# DD2090_4CAM_FFC_Connector_B.net
KiCad netlist of a schematic drawn in Altium Designer
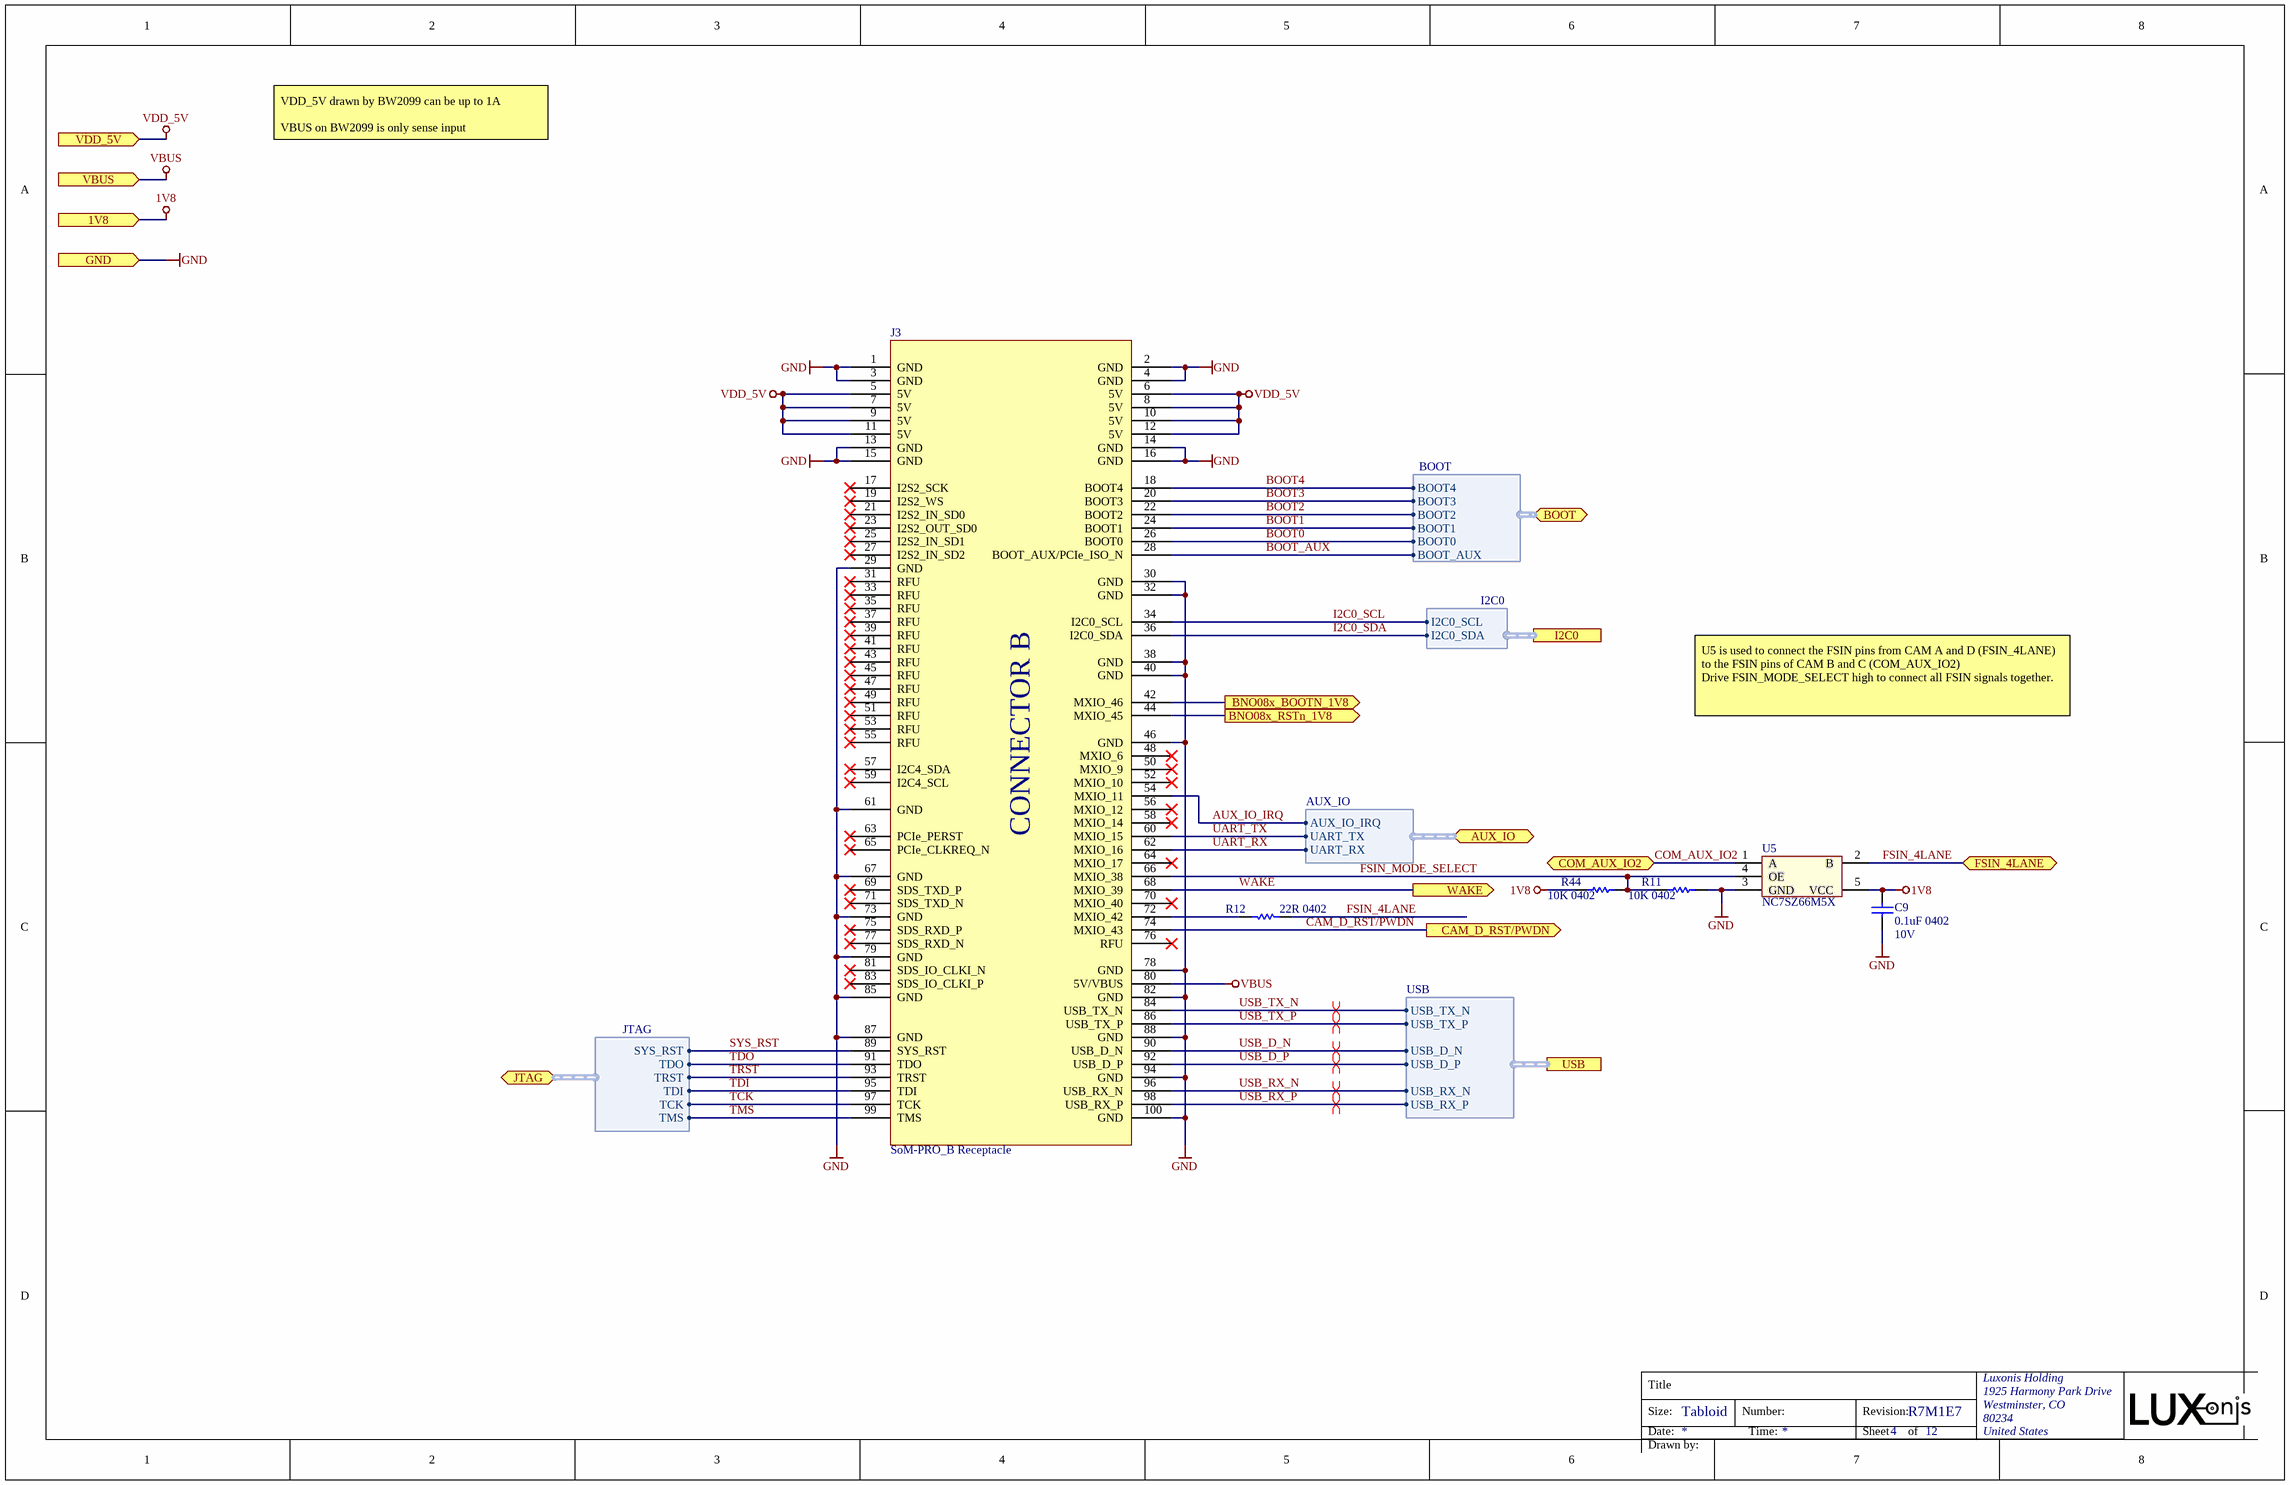
[diagram p0: DD2090_4CAM_FFC_Connector_B.SchDoc]

(export (version "E")
  (design (tool "Eeschema 10.0.6"))
  (components
    (comp (ref "C9")
      (value "0.1uF 0402")
      (footprint "CAPC0402(1005)70_L")
      (description "CAP CER 0.1UF 10V X7R 0402 5%")
      (fields (field (name "TOLERANCE") "5%") (field (name "VOLTAGE RATING") "10V"))
      (libsource (lib "LuxonisMaster") (part "GRM155R71A104JA01D"))
    )
    (comp (ref "J3")
      (value "SoM-PRO_B Receptacle")
      (footprint "LuxonisMaster:CON_B_BW2099_SoM_DF40HC-3.0-100DS-0.4V_minpad")
      (description "CONN RCPT 100POS 0.4MM SMD GOLD")
      (libsource (lib "LuxonisMaster") (part "DF40HC(3.0)-100DS-0.4V_SoM-PRO_B"))
    )
    (comp (ref "R11")
      (value "10K 0402")
      (footprint "RESC0402(1005)_L")
      (fields (field (name "TOLERANCE") "1%"))
      (libsource (lib "LuxonisMaster") (part "RC0402FR-1310KL"))
    )
    (comp (ref "R12")
      (value "22R 0402")
      (footprint "RESC0402(1005)_N")
      (description "RES SMD 22 OHM 1% 1/16W 0402")
      (fields (field (name "TOLERANCE") "1%"))
      (libsource (lib "BW2098POE") (part "RC0402FR-0722RL"))
    )
    (comp (ref "R44")
      (value "10K 0402")
      (footprint "RESC0402(1005)_L")
      (fields (field (name "TOLERANCE") "1%"))
      (libsource (lib "LuxonisMaster") (part "RC0402FR-1310KL"))
    )
    (comp (ref "U5")
      (value "NC7SZ66M5X")
      (footprint "SOT235")
      (fields (field (name "VOLTAGE") "5V"))
      (libsource (lib "DD2099_4CAM_FFC") (part "NC7SZ66M5X"))
    )
  )
  (nets
    (net (code "6") (name "/AUX_IO_IRQ") (class "Default")
      (node (ref "J3") (pin "54") (pinfunction "MXIO_11_54") (pintype "passive"))
    )
    (net (code "7") (name "/BNO08x_BOOTN_1V8") (class "Default")
      (node (ref "J3") (pin "42") (pinfunction "MXIO_46_42") (pintype "passive"))
    )
    (net (code "8") (name "/BNO08x_RSTn_1V8") (class "Default")
      (node (ref "J3") (pin "44") (pinfunction "MXIO_45_44") (pintype "passive"))
    )
    (net (code "9") (name "/BOOT0") (class "Default")
      (node (ref "J3") (pin "26") (pinfunction "BOOT0_26") (pintype "passive"))
    )
    (net (code "10") (name "/BOOT1") (class "Default")
      (node (ref "J3") (pin "24") (pinfunction "BOOT1_24") (pintype "passive"))
    )
    (net (code "11") (name "/BOOT2") (class "Default")
      (node (ref "J3") (pin "22") (pinfunction "BOOT2_22") (pintype "passive"))
    )
    (net (code "12") (name "/BOOT3") (class "Default")
      (node (ref "J3") (pin "20") (pinfunction "BOOT3_20") (pintype "passive"))
    )
    (net (code "13") (name "/BOOT4") (class "Default")
      (node (ref "J3") (pin "18") (pinfunction "BOOT4_18") (pintype "passive"))
    )
    (net (code "14") (name "/BOOT_AUX") (class "Default")
      (node (ref "J3") (pin "28") (pinfunction "BOOT_AUX/PCIe_ISO_N_28") (pintype "passive"))
    )
    (net (code "15") (name "/CAM_D_RST{slash}PWDN") (class "Default")
      (node (ref "J3") (pin "74") (pinfunction "MXIO_43_74") (pintype "passive"))
    )
    (net (code "16") (name "/COM_AUX_IO2") (class "Default")
      (node (ref "U5") (pin "1") (pinfunction "A_1") (pintype "passive"))
    )
    (net (code "17") (name "/FSIN_4LANE") (class "Default")
      (node (ref "R12") (pin "1") (pinfunction "1_1") (pintype "passive"))
      (node (ref "U5") (pin "2") (pinfunction "B_2") (pintype "passive"))
    )
    (net (code "18") (name "/FSIN_MODE_SELECT") (class "Default")
      (node (ref "J3") (pin "66") (pinfunction "MXIO_38_66") (pintype "passive"))
      (node (ref "R11") (pin "2") (pinfunction "2_2") (pintype "passive"))
      (node (ref "R44") (pin "1") (pinfunction "1_1") (pintype "passive"))
      (node (ref "U5") (pin "4") (pinfunction "OE_4") (pintype "passive"))
    )
    (net (code "19") (name "/I2C0_SCL") (class "Default")
      (node (ref "J3") (pin "34") (pinfunction "I2C0_SCL_34") (pintype "passive"))
    )
    (net (code "20") (name "/I2C0_SDA") (class "Default")
      (node (ref "J3") (pin "36") (pinfunction "I2C0_SDA_36") (pintype "passive"))
    )
    (net (code "21") (name "/SYS_RST") (class "Default")
      (node (ref "J3") (pin "89") (pinfunction "SYS_RST_89") (pintype "passive"))
    )
    (net (code "22") (name "/TCK") (class "Default")
      (node (ref "J3") (pin "97") (pinfunction "TCK_97") (pintype "passive"))
    )
    (net (code "23") (name "/TDI") (class "Default")
      (node (ref "J3") (pin "95") (pinfunction "TDI_95") (pintype "passive"))
    )
    (net (code "24") (name "/TDO") (class "Default")
      (node (ref "J3") (pin "91") (pinfunction "TDO_91") (pintype "passive"))
    )
    (net (code "25") (name "/TMS") (class "Default")
      (node (ref "J3") (pin "99") (pinfunction "TMS_99") (pintype "passive"))
    )
    (net (code "26") (name "/TRST") (class "Default")
      (node (ref "J3") (pin "93") (pinfunction "TRST_93") (pintype "passive"))
    )
    (net (code "27") (name "/UART_RX") (class "Default")
      (node (ref "J3") (pin "62") (pinfunction "MXIO_16_62") (pintype "passive"))
    )
    (net (code "28") (name "/UART_TX") (class "Default")
      (node (ref "J3") (pin "60") (pinfunction "MXIO_15_60") (pintype "passive"))
    )
    (net (code "29") (name "/USB_D_N") (class "Default")
      (node (ref "J3") (pin "90") (pinfunction "USB_D_N_90") (pintype "passive"))
    )
    (net (code "30") (name "/USB_D_P") (class "Default")
      (node (ref "J3") (pin "92") (pinfunction "USB_D_P_92") (pintype "passive"))
    )
    (net (code "31") (name "/USB_RX_N") (class "Default")
      (node (ref "J3") (pin "96") (pinfunction "USB_RX_N_96") (pintype "passive"))
    )
    (net (code "32") (name "/USB_RX_P") (class "Default")
      (node (ref "J3") (pin "98") (pinfunction "USB_RX_P_98") (pintype "passive"))
    )
    (net (code "33") (name "/USB_TX_N") (class "Default")
      (node (ref "J3") (pin "84") (pinfunction "USB_TX_N_84") (pintype "passive"))
    )
    (net (code "34") (name "/USB_TX_P") (class "Default")
      (node (ref "J3") (pin "86") (pinfunction "USB_TX_P_86") (pintype "passive"))
    )
    (net (code "35") (name "/WAKE") (class "Default")
      (node (ref "J3") (pin "68") (pinfunction "MXIO_39_68") (pintype "passive"))
    )
    (net (code "41") (name "1V8") (class "Default")
      (node (ref "C9") (pin "2") (pinfunction "2_2") (pintype "passive"))
      (node (ref "R44") (pin "2") (pinfunction "2_2") (pintype "passive"))
      (node (ref "U5") (pin "5") (pinfunction "VCC_5") (pintype "passive"))
    )
    (net (code "42") (name "GND") (class "Default")
      (node (ref "C9") (pin "1") (pinfunction "1_1") (pintype "passive"))
      (node (ref "J3") (pin "1") (pinfunction "GND_1") (pintype "passive"))
      (node (ref "J3") (pin "100") (pinfunction "GND_100") (pintype "passive"))
      (node (ref "J3") (pin "13") (pinfunction "GND_13") (pintype "passive"))
      (node (ref "J3") (pin "14") (pinfunction "GND_14") (pintype "passive"))
      (node (ref "J3") (pin "15") (pinfunction "GND_15") (pintype "passive"))
      (node (ref "J3") (pin "16") (pinfunction "GND_16") (pintype "passive"))
      (node (ref "J3") (pin "2") (pinfunction "GND_2") (pintype "passive"))
      (node (ref "J3") (pin "29") (pinfunction "GND_29") (pintype "passive"))
      (node (ref "J3") (pin "3") (pinfunction "GND_3") (pintype "passive"))
      (node (ref "J3") (pin "30") (pinfunction "GND_30") (pintype "passive"))
      (node (ref "J3") (pin "32") (pinfunction "GND_32") (pintype "passive"))
      (node (ref "J3") (pin "38") (pinfunction "GND_38") (pintype "passive"))
      (node (ref "J3") (pin "4") (pinfunction "GND_4") (pintype "passive"))
      (node (ref "J3") (pin "40") (pinfunction "GND_40") (pintype "passive"))
      (node (ref "J3") (pin "46") (pinfunction "GND_46") (pintype "passive"))
      (node (ref "J3") (pin "61") (pinfunction "GND_61") (pintype "passive"))
      (node (ref "J3") (pin "67") (pinfunction "GND_67") (pintype "passive"))
      (node (ref "J3") (pin "73") (pinfunction "GND_73") (pintype "passive"))
      (node (ref "J3") (pin "78") (pinfunction "GND_78") (pintype "passive"))
      (node (ref "J3") (pin "79") (pinfunction "GND_79") (pintype "passive"))
      (node (ref "J3") (pin "82") (pinfunction "GND_82") (pintype "passive"))
      (node (ref "J3") (pin "85") (pinfunction "GND_85") (pintype "passive"))
      (node (ref "J3") (pin "87") (pinfunction "GND_87") (pintype "passive"))
      (node (ref "J3") (pin "88") (pinfunction "GND_88") (pintype "passive"))
      (node (ref "J3") (pin "94") (pinfunction "GND_94") (pintype "passive"))
      (node (ref "R11") (pin "1") (pinfunction "1_1") (pintype "passive"))
      (node (ref "U5") (pin "3") (pinfunction "GND_3") (pintype "passive"))
    )
    (net (code "43") (name "Net-(J3-MXIO_42)") (class "Default")
      (node (ref "J3") (pin "72") (pinfunction "MXIO_42_72") (pintype "passive"))
      (node (ref "R12") (pin "2") (pinfunction "2_2") (pintype "passive"))
    )
    (net (code "44") (name "VBUS") (class "Default")
      (node (ref "J3") (pin "80") (pinfunction "5V/VBUS_80") (pintype "passive"))
    )
    (net (code "45") (name "VDD_5V") (class "Default")
      (node (ref "J3") (pin "10") (pinfunction "5V_10") (pintype "passive"))
      (node (ref "J3") (pin "11") (pinfunction "5V_11") (pintype "passive"))
      (node (ref "J3") (pin "12") (pinfunction "5V_12") (pintype "passive"))
      (node (ref "J3") (pin "5") (pinfunction "5V_5") (pintype "passive"))
      (node (ref "J3") (pin "6") (pinfunction "5V_6") (pintype "passive"))
      (node (ref "J3") (pin "7") (pinfunction "5V_7") (pintype "passive"))
      (node (ref "J3") (pin "8") (pinfunction "5V_8") (pintype "passive"))
      (node (ref "J3") (pin "9") (pinfunction "5V_9") (pintype "passive"))
    )
    (net (code "46") (name "unconnected-(J3-I2C4_SCL-Pad59)") (class "Default")
      (node (ref "J3") (pin "59") (pinfunction "I2C4_SCL_59") (pintype "passive+no_connect"))
    )
    (net (code "47") (name "unconnected-(J3-I2C4_SDA-Pad57)") (class "Default")
      (node (ref "J3") (pin "57") (pinfunction "I2C4_SDA_57") (pintype "passive+no_connect"))
    )
    (net (code "48") (name "unconnected-(J3-I2S2_IN_SD0-Pad21)") (class "Default")
      (node (ref "J3") (pin "21") (pinfunction "I2S2_IN_SD0_21") (pintype "passive+no_connect"))
    )
    (net (code "49") (name "unconnected-(J3-I2S2_IN_SD1-Pad25)") (class "Default")
      (node (ref "J3") (pin "25") (pinfunction "I2S2_IN_SD1_25") (pintype "passive+no_connect"))
    )
    (net (code "50") (name "unconnected-(J3-I2S2_IN_SD2-Pad27)") (class "Default")
      (node (ref "J3") (pin "27") (pinfunction "I2S2_IN_SD2_27") (pintype "passive+no_connect"))
    )
    (net (code "51") (name "unconnected-(J3-I2S2_OUT_SD0-Pad23)") (class "Default")
      (node (ref "J3") (pin "23") (pinfunction "I2S2_OUT_SD0_23") (pintype "passive+no_connect"))
    )
    (net (code "52") (name "unconnected-(J3-I2S2_SCK-Pad17)") (class "Default")
      (node (ref "J3") (pin "17") (pinfunction "I2S2_SCK_17") (pintype "passive+no_connect"))
    )
    (net (code "53") (name "unconnected-(J3-I2S2_WS-Pad19)") (class "Default")
      (node (ref "J3") (pin "19") (pinfunction "I2S2_WS_19") (pintype "passive+no_connect"))
    )
    (net (code "54") (name "unconnected-(J3-MXIO_6-Pad48)") (class "Default")
      (node (ref "J3") (pin "48") (pinfunction "MXIO_6_48") (pintype "passive+no_connect"))
    )
    (net (code "55") (name "unconnected-(J3-MXIO_9-Pad50)") (class "Default")
      (node (ref "J3") (pin "50") (pinfunction "MXIO_9_50") (pintype "passive+no_connect"))
    )
    (net (code "56") (name "unconnected-(J3-MXIO_10-Pad52)") (class "Default")
      (node (ref "J3") (pin "52") (pinfunction "MXIO_10_52") (pintype "passive+no_connect"))
    )
    (net (code "57") (name "unconnected-(J3-MXIO_12-Pad56)") (class "Default")
      (node (ref "J3") (pin "56") (pinfunction "MXIO_12_56") (pintype "passive+no_connect"))
    )
    (net (code "58") (name "unconnected-(J3-MXIO_14-Pad58)") (class "Default")
      (node (ref "J3") (pin "58") (pinfunction "MXIO_14_58") (pintype "passive+no_connect"))
    )
    (net (code "59") (name "unconnected-(J3-MXIO_17-Pad64)") (class "Default")
      (node (ref "J3") (pin "64") (pinfunction "MXIO_17_64") (pintype "passive+no_connect"))
    )
    (net (code "60") (name "unconnected-(J3-MXIO_40-Pad70)") (class "Default")
      (node (ref "J3") (pin "70") (pinfunction "MXIO_40_70") (pintype "passive+no_connect"))
    )
    (net (code "61") (name "unconnected-(J3-PCIe_CLKREQ_N-Pad65)") (class "Default")
      (node (ref "J3") (pin "65") (pinfunction "PCIe_CLKREQ_N_65") (pintype "passive+no_connect"))
    )
    (net (code "62") (name "unconnected-(J3-PCIe_PERST-Pad63)") (class "Default")
      (node (ref "J3") (pin "63") (pinfunction "PCIe_PERST_63") (pintype "passive+no_connect"))
    )
    (net (code "63") (name "unconnected-(J3-RFU-Pad31)") (class "Default")
      (node (ref "J3") (pin "31") (pinfunction "RFU_31") (pintype "passive+no_connect"))
    )
    (net (code "64") (name "unconnected-(J3-RFU-Pad33)") (class "Default")
      (node (ref "J3") (pin "33") (pinfunction "RFU_33") (pintype "passive+no_connect"))
    )
    (net (code "65") (name "unconnected-(J3-RFU-Pad35)") (class "Default")
      (node (ref "J3") (pin "35") (pinfunction "RFU_35") (pintype "passive+no_connect"))
    )
    (net (code "66") (name "unconnected-(J3-RFU-Pad37)") (class "Default")
      (node (ref "J3") (pin "37") (pinfunction "RFU_37") (pintype "passive+no_connect"))
    )
    (net (code "67") (name "unconnected-(J3-RFU-Pad39)") (class "Default")
      (node (ref "J3") (pin "39") (pinfunction "RFU_39") (pintype "passive+no_connect"))
    )
    (net (code "68") (name "unconnected-(J3-RFU-Pad41)") (class "Default")
      (node (ref "J3") (pin "41") (pinfunction "RFU_41") (pintype "passive+no_connect"))
    )
    (net (code "69") (name "unconnected-(J3-RFU-Pad43)") (class "Default")
      (node (ref "J3") (pin "43") (pinfunction "RFU_43") (pintype "passive+no_connect"))
    )
    (net (code "70") (name "unconnected-(J3-RFU-Pad45)") (class "Default")
      (node (ref "J3") (pin "45") (pinfunction "RFU_45") (pintype "passive+no_connect"))
    )
    (net (code "71") (name "unconnected-(J3-RFU-Pad47)") (class "Default")
      (node (ref "J3") (pin "47") (pinfunction "RFU_47") (pintype "passive+no_connect"))
    )
    (net (code "72") (name "unconnected-(J3-RFU-Pad49)") (class "Default")
      (node (ref "J3") (pin "49") (pinfunction "RFU_49") (pintype "passive+no_connect"))
    )
    (net (code "73") (name "unconnected-(J3-RFU-Pad51)") (class "Default")
      (node (ref "J3") (pin "51") (pinfunction "RFU_51") (pintype "passive+no_connect"))
    )
    (net (code "74") (name "unconnected-(J3-RFU-Pad53)") (class "Default")
      (node (ref "J3") (pin "53") (pinfunction "RFU_53") (pintype "passive+no_connect"))
    )
    (net (code "75") (name "unconnected-(J3-RFU-Pad55)") (class "Default")
      (node (ref "J3") (pin "55") (pinfunction "RFU_55") (pintype "passive+no_connect"))
    )
    (net (code "76") (name "unconnected-(J3-RFU-Pad76)") (class "Default")
      (node (ref "J3") (pin "76") (pinfunction "RFU_76") (pintype "passive+no_connect"))
    )
    (net (code "77") (name "unconnected-(J3-SDS_IO_CLKI_N-Pad81)") (class "Default")
      (node (ref "J3") (pin "81") (pinfunction "SDS_IO_CLKI_N_81") (pintype "passive+no_connect"))
    )
    (net (code "78") (name "unconnected-(J3-SDS_IO_CLKI_P-Pad83)") (class "Default")
      (node (ref "J3") (pin "83") (pinfunction "SDS_IO_CLKI_P_83") (pintype "passive+no_connect"))
    )
    (net (code "79") (name "unconnected-(J3-SDS_RXD_N-Pad77)") (class "Default")
      (node (ref "J3") (pin "77") (pinfunction "SDS_RXD_N_77") (pintype "passive+no_connect"))
    )
    (net (code "80") (name "unconnected-(J3-SDS_RXD_P-Pad75)") (class "Default")
      (node (ref "J3") (pin "75") (pinfunction "SDS_RXD_P_75") (pintype "passive+no_connect"))
    )
    (net (code "81") (name "unconnected-(J3-SDS_TXD_N-Pad71)") (class "Default")
      (node (ref "J3") (pin "71") (pinfunction "SDS_TXD_N_71") (pintype "passive+no_connect"))
    )
    (net (code "82") (name "unconnected-(J3-SDS_TXD_P-Pad69)") (class "Default")
      (node (ref "J3") (pin "69") (pinfunction "SDS_TXD_P_69") (pintype "passive+no_connect"))
    )
  )
)
